# Motor_Connection.net
KiCad netlist of a schematic drawn in Altium Designer
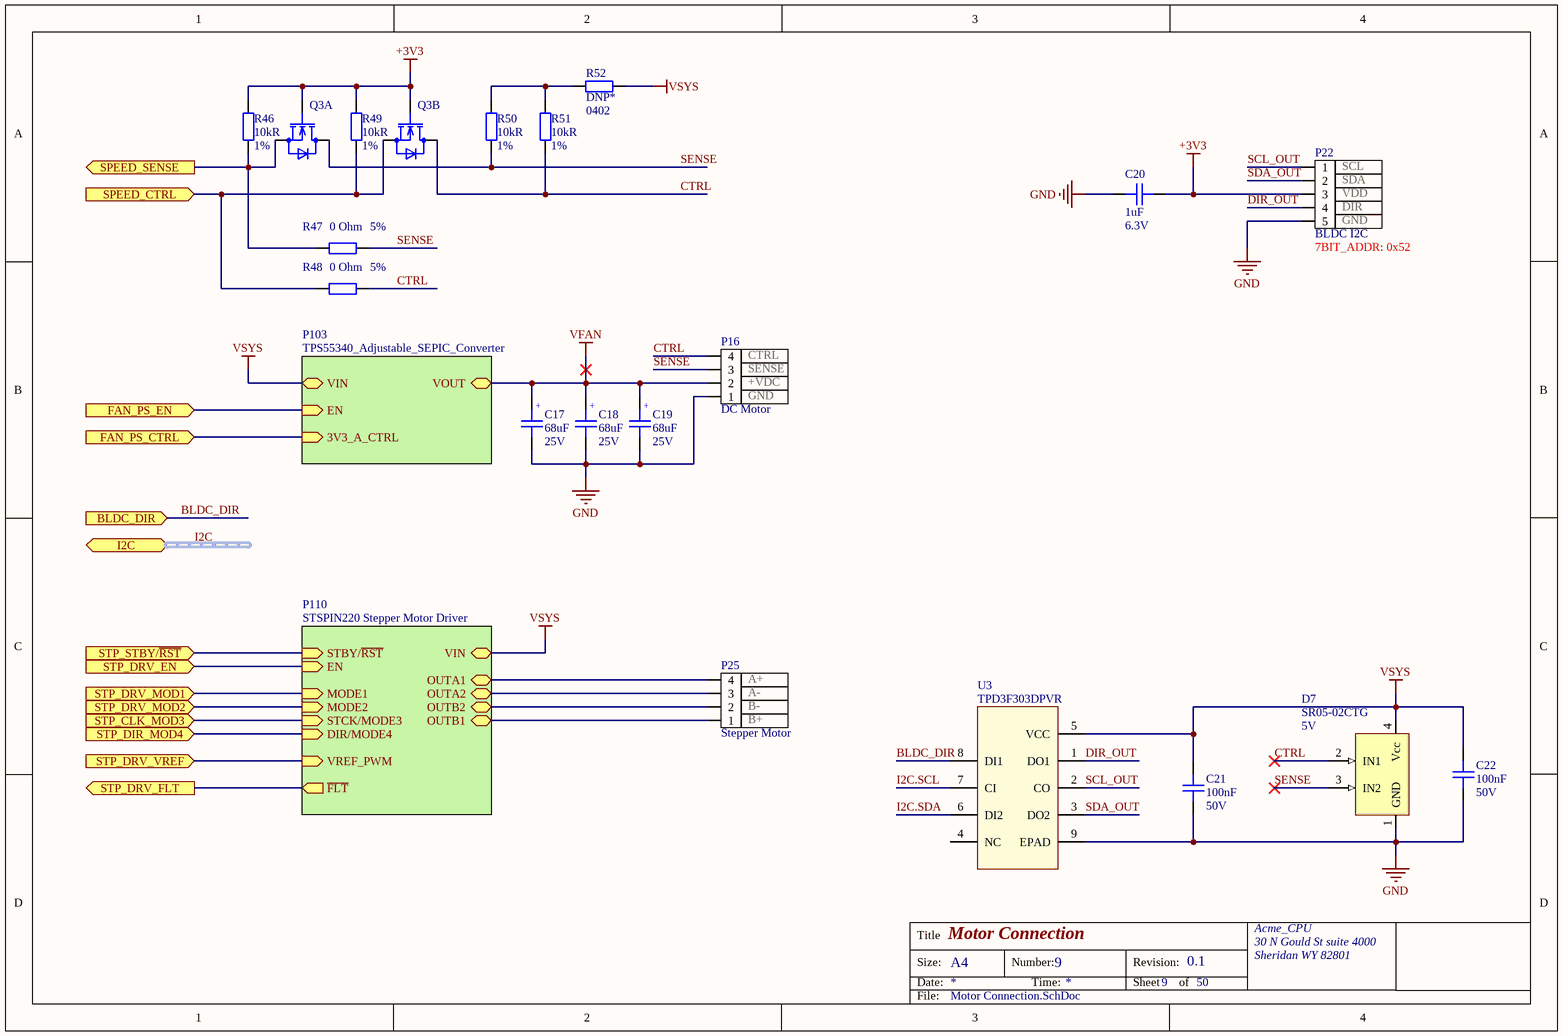
[diagram p0: Motor Connection.SchDoc]

(export (version "E")
  (design (tool "Eeschema 10.0.6"))
  (components
    (comp (ref "C17")
      (value "CAP ALUM 68 UF 20% 25 V SMD")
      (footprint "WCAP-ASLI_6.3x5.5")
      (description "68µF 25V Aluminum Electrolytic Capacitors Radial, Can - SMD  2000 Hrs @ 105°C")
      (fields
        (field (name "MANUFACTURER") "Wurth Elektronik")
        (field (name "MANUFACTURER PART NUMBER") "865080443009")
        (field (name "CAPACITANCE") "68uF")
        (field (name "RATED VOLTAGE") "25V")
      )
      (libsource (lib "capacitors_alum_electr_poly") (part "CAP ALUM 68 UF 20% 25 V SMD"))
    )
    (comp (ref "C18")
      (value "CAP ALUM 68 UF 20% 25 V SMD")
      (footprint "WCAP-ASLI_6.3x5.5")
      (description "68µF 25V Aluminum Electrolytic Capacitors Radial, Can - SMD  2000 Hrs @ 105°C")
      (fields
        (field (name "MANUFACTURER") "Wurth Elektronik")
        (field (name "MANUFACTURER PART NUMBER") "865080443009")
        (field (name "CAPACITANCE") "68uF")
        (field (name "RATED VOLTAGE") "25V")
      )
      (libsource (lib "capacitors_alum_electr_poly") (part "CAP ALUM 68 UF 20% 25 V SMD"))
    )
    (comp (ref "C19")
      (value "CAP ALUM 68 UF 20% 25 V SMD")
      (footprint "WCAP-ASLI_6.3x5.5")
      (description "68µF 25V Aluminum Electrolytic Capacitors Radial, Can - SMD  2000 Hrs @ 105°C")
      (fields
        (field (name "MANUFACTURER") "Wurth Elektronik")
        (field (name "MANUFACTURER PART NUMBER") "865080443009")
        (field (name "CAPACITANCE") "68uF")
        (field (name "RATED VOLTAGE") "25V")
      )
      (libsource (lib "capacitors_alum_electr_poly") (part "CAP ALUM 68 UF 20% 25 V SMD"))
    )
    (comp (ref "C20")
      (value "CAP CER 1UF 6.3V X5R 0402")
      (footprint "C0402")
      (description "1µF ±10% 6.3V Ceramic Capacitor X5R 0402 (1005 Metric)")
      (fields
        (field (name "MANUFACTURER") "Yageo")
        (field (name "MANUFACTURER PART NUMBER") "CC0402KRX5R5BB105")
        (field (name "CAPACITANCE") "1uF")
        (field (name "VOLTAGE RATING") "6.3V")
      )
      (libsource (lib "capacitors_smd") (part "CAP CER 1UF 6.3V X5R 0402"))
    )
    (comp (ref "C21")
      (value "CAP CER 0.1UF 50V X7R 0402")
      (footprint "C0402")
      (description "0.1µF ±10% 50V Ceramic Capacitor X7R 0402 (1005 Metric)")
      (fields
        (field (name "MANUFACTURER") "TDK")
        (field (name "MANUFACTURER PART NUMBER") "CGA2B3X7R1H104K050BB")
        (field (name "CAPACITANCE") "100nF")
        (field (name "VOLTAGE") "50V")
      )
      (libsource (lib "capacitors_smd") (part "CAP CER 0.1UF 50V X7R 0402"))
    )
    (comp (ref "C22")
      (value "CAP CER 0.1UF 50V X7R 0402")
      (footprint "C0402")
      (description "0.1µF ±10% 50V Ceramic Capacitor X7R 0402 (1005 Metric)")
      (fields
        (field (name "MANUFACTURER") "TDK")
        (field (name "MANUFACTURER PART NUMBER") "CGA2B3X7R1H104K050BB")
        (field (name "CAPACITANCE") "100nF")
        (field (name "VOLTAGE") "50V")
      )
      (libsource (lib "capacitors_smd") (part "CAP CER 0.1UF 50V X7R 0402"))
    )
    (comp (ref "D7")
      (value "SR05-02CTG")
      (footprint "SOT-143")
      (description "TVS DIODE 5VWM 18VC SOT143")
      (fields (field (name "MANUFACTURER") "Littelfuse") (field (name "REVERSE STANDOFF VOLTAGE") "5V"))
      (libsource (lib "diodes_tvs") (part "TVS DIODE 5VWM 18VC SOT143"))
    )
    (comp (ref "P16")
      (value "DC Motor")
      (footprint "CONN_S4B-ZR(LF)(SN)")
      (description "Connector Header Through Hole, Right Angle 4 position 0.059\" (1.50mm)")
      (fields
        (field (name "MANUFACTURER") "JST")
        (field (name "MANUFACTURER PART NUMBER") "S4B-ZR(LF)(SN)")
        (field (name "PIN_1") "GND")
        (field (name "PIN_2") "+VDC")
        (field (name "PIN_3") "SENSE")
        (field (name "PIN_4") "CTRL")
      )
      (libsource (lib "connectors_header") (part "CONN HEADER TH R/A 4POS 1.5MM"))
    )
    (comp (ref "P22")
      (value "BLDC I2C")
      (footprint "CONN_S5B-ZR(LF)(SN)")
      (description "Connector Header Through Hole, Right Angle 5 position 0.059\" (1.50mm)")
      (fields
        (field (name "MANUFACTURER") "JST")
        (field (name "MANUFACTURER PART NUMBER") "S5B-ZR(LF)(SN)")
        (field (name "PIN_1") "SCL")
        (field (name "PIN_2") "SDA")
        (field (name "PIN_3") "VDD")
        (field (name "PIN_4") "DIR")
        (field (name "PIN_5") "GND")
        (field (name "7BIT_ADDR") "0x52")
      )
      (libsource (lib "connectors_header") (part "CONN HEADER TH R/A 5POS 1.5MM"))
    )
    (comp (ref "P25")
      (value "Stepper Motor")
      (footprint "CONN_S4B-ZR(LF)(SN)")
      (description "Connector Header Through Hole, Right Angle 4 position 0.059\" (1.50mm)")
      (fields
        (field (name "MANUFACTURER") "JST")
        (field (name "MANUFACTURER PART NUMBER") "S4B-ZR(LF)(SN)")
        (field (name "PIN_1") "B+")
        (field (name "PIN_2") "B-")
        (field (name "PIN_3") "A-")
        (field (name "PIN_4") "A+")
      )
      (libsource (lib "connectors_header") (part "CONN HEADER TH R/A 4POS 1.5MM"))
    )
    (comp (ref "Q3")
      (value "DMN32D2LV-7")
      (footprint "SON_400UV-7_DIO")
      (description "Mosfet Array 2 N-Channel (Dual) 30V 400mA 400mW Surface Mount SOT-563")
      (fields (field (name "MANUFACTURER") "Diodes"))
      (libsource (lib "mosfets") (part "ARRAY MOSFET 2N-CH 30V 0.4A SOT-563"))
    )
    (comp (ref "R46")
      (value "RES SMD 10K OHM 1% 1/16W 0402")
      (footprint "R0402")
      (description "10 kOhms ±1% 0.063W, 1/16W Chip Resistor 0402 (1005 Metric) Moisture Resistant Thick Film")
      (fields
        (field (name "MANUFACTURER PART NUMBER") "RC0402FR-0710KP")
        (field (name "MANUFACTURER") "Yageo")
        (field (name "RESISTANCE") "10kR")
        (field (name "TOLERANCE") "1%")
      )
      (libsource (lib "resistors_smd") (part "RES SMD 10K OHM 1% 1/16W 0402"))
    )
    (comp (ref "R47")
      (value "RES SMD 0 OHM JUMPER 1/16W 0402")
      (footprint "R0402")
      (description "0 Ohms Jumper 0.063W, 1/16W Chip Resistor 0402 (1005 Metric) Moisture Resistant Thick Film")
      (fields
        (field (name "MANUFACTURER") "Yageo")
        (field (name "MANUFACTURER PART NUMBER") "RC0402JR-070RL")
        (field (name "TOLERANCE") "5%")
        (field (name "RESISTANCE") "0 Ohm")
      )
      (libsource (lib "resistors_smd") (part "RES SMD 0 OHM JUMPER 1/16W 0402"))
    )
    (comp (ref "R48")
      (value "RES SMD 0 OHM JUMPER 1/16W 0402")
      (footprint "R0402")
      (description "0 Ohms Jumper 0.063W, 1/16W Chip Resistor 0402 (1005 Metric) Moisture Resistant Thick Film")
      (fields
        (field (name "MANUFACTURER") "Yageo")
        (field (name "MANUFACTURER PART NUMBER") "RC0402JR-070RL")
        (field (name "TOLERANCE") "5%")
        (field (name "RESISTANCE") "0 Ohm")
      )
      (libsource (lib "resistors_smd") (part "RES SMD 0 OHM JUMPER 1/16W 0402"))
    )
    (comp (ref "R49")
      (value "RES SMD 10K OHM 1% 1/16W 0402")
      (footprint "R0402")
      (description "10 kOhms ±1% 0.063W, 1/16W Chip Resistor 0402 (1005 Metric) Moisture Resistant Thick Film")
      (fields
        (field (name "MANUFACTURER PART NUMBER") "RC0402FR-0710KP")
        (field (name "MANUFACTURER") "Yageo")
        (field (name "RESISTANCE") "10kR")
        (field (name "TOLERANCE") "1%")
      )
      (libsource (lib "resistors_smd") (part "RES SMD 10K OHM 1% 1/16W 0402"))
    )
    (comp (ref "R50")
      (value "RES SMD 10K OHM 1% 1/16W 0402")
      (footprint "R0402")
      (description "10 kOhms ±1% 0.063W, 1/16W Chip Resistor 0402 (1005 Metric) Moisture Resistant Thick Film")
      (fields
        (field (name "MANUFACTURER PART NUMBER") "RC0402FR-0710KP")
        (field (name "MANUFACTURER") "Yageo")
        (field (name "RESISTANCE") "10kR")
        (field (name "TOLERANCE") "1%")
      )
      (libsource (lib "resistors_smd") (part "RES SMD 10K OHM 1% 1/16W 0402"))
    )
    (comp (ref "R51")
      (value "RES SMD 10K OHM 1% 1/16W 0402")
      (footprint "R0402")
      (description "10 kOhms ±1% 0.063W, 1/16W Chip Resistor 0402 (1005 Metric) Moisture Resistant Thick Film")
      (fields
        (field (name "MANUFACTURER PART NUMBER") "RC0402FR-0710KP")
        (field (name "MANUFACTURER") "Yageo")
        (field (name "RESISTANCE") "10kR")
        (field (name "TOLERANCE") "1%")
      )
      (libsource (lib "resistors_smd") (part "RES SMD 10K OHM 1% 1/16W 0402"))
    )
    (comp (ref "R52")
      (value "DNP*")
      (footprint "R0402")
      (description "Placeholder for a 0402 resistor")
      (fields (field (name "CASE/PACKAGE") "0402"))
      (libsource (lib "resistors_smd") (part "RES SMD NO BOM 0402"))
    )
    (comp (ref "U3")
      (value "TPD3F303DPVR")
      (footprint "DPV8_1P7X0P4")
      (description "RC (Pi) EMI Filter 2nd Order Low Pass 3 Channel R = 47Ohms, 100Ohms, C = 20pF  8-UFDFN Exposed Pad")
      (fields (field (name "MANUFACTURER") "Texas Instruments"))
      (libsource (lib "diodes_tvs") (part "FILTER RC(PI) ESD SMD  8-UFDFN EP"))
    )
  )
  (nets
    (net (code "2") (name "+3V3") (class "Default")
      (node (ref "C20") (pin "2") (pinfunction "2_2") (pintype "passive"))
      (node (ref "P22") (pin "3") (pinfunction "3_3") (pintype "passive"))
      (node (ref "Q3") (pin "2") (pinfunction "G_2") (pintype "passive"))
      (node (ref "Q3") (pin "5") (pinfunction "G_5") (pintype "passive"))
      (node (ref "R46") (pin "1") (pinfunction "1_1") (pintype "passive"))
      (node (ref "R49") (pin "1") (pinfunction "1_1") (pintype "passive"))
    )
    (net (code "3") (name "/BLDC_DIR") (class "Default")
      (node (ref "U3") (pin "8") (pinfunction "DI1_8") (pintype "passive"))
    )
    (net (code "4") (name "/CTRL") (class "Default")
      (node (ref "D7") (pin "2") (pinfunction "IN1_2") (pintype "input"))
      (node (ref "P16") (pin "4") (pinfunction "4_4") (pintype "passive"))
      (node (ref "Q3") (pin "3") (pinfunction "D_3") (pintype "passive"))
      (node (ref "R48") (pin "2") (pinfunction "2_2") (pintype "passive"))
      (node (ref "R51") (pin "2") (pinfunction "2_2") (pintype "passive"))
    )
    (net (code "5") (name "/DIR_OUT") (class "Default")
      (node (ref "P22") (pin "4") (pinfunction "4_4") (pintype "passive"))
      (node (ref "U3") (pin "1") (pinfunction "DO1_1") (pintype "passive"))
    )
    (net (code "8") (name "/I2C.SCL") (class "Default")
      (node (ref "U3") (pin "7") (pinfunction "CI_7") (pintype "passive"))
    )
    (net (code "9") (name "/I2C.SDA") (class "Default")
      (node (ref "U3") (pin "6") (pinfunction "DI2_6") (pintype "passive"))
    )
    (net (code "10") (name "/OUTA1") (class "Default")
      (node (ref "P25") (pin "4") (pinfunction "4_4") (pintype "passive"))
    )
    (net (code "11") (name "/OUTA2") (class "Default")
      (node (ref "P25") (pin "3") (pinfunction "3_3") (pintype "passive"))
    )
    (net (code "12") (name "/OUTB1") (class "Default")
      (node (ref "P25") (pin "1") (pinfunction "1_1") (pintype "passive"))
    )
    (net (code "13") (name "/OUTB2") (class "Default")
      (node (ref "P25") (pin "2") (pinfunction "2_2") (pintype "passive"))
    )
    (net (code "14") (name "/SCL_OUT") (class "Default")
      (node (ref "P22") (pin "1") (pinfunction "1_1") (pintype "passive"))
      (node (ref "U3") (pin "2") (pinfunction "CO_2") (pintype "passive"))
    )
    (net (code "15") (name "/SDA_OUT") (class "Default")
      (node (ref "P22") (pin "2") (pinfunction "2_2") (pintype "passive"))
      (node (ref "U3") (pin "3") (pinfunction "DO2_3") (pintype "passive"))
    )
    (net (code "16") (name "/SENSE") (class "Default")
      (node (ref "D7") (pin "3") (pinfunction "IN2_3") (pintype "input"))
      (node (ref "P16") (pin "3") (pinfunction "3_3") (pintype "passive"))
      (node (ref "Q3") (pin "6") (pinfunction "D_6") (pintype "passive"))
      (node (ref "R47") (pin "2") (pinfunction "2_2") (pintype "passive"))
      (node (ref "R50") (pin "2") (pinfunction "2_2") (pintype "passive"))
    )
    (net (code "17") (name "/SPEED_CTRL") (class "Default")
      (node (ref "Q3") (pin "4") (pinfunction "S_4") (pintype "passive"))
      (node (ref "R48") (pin "1") (pinfunction "1_1") (pintype "passive"))
      (node (ref "R49") (pin "2") (pinfunction "2_2") (pintype "passive"))
    )
    (net (code "18") (name "/SPEED_SENSE") (class "Default")
      (node (ref "Q3") (pin "1") (pinfunction "S_1") (pintype "passive"))
      (node (ref "R46") (pin "2") (pinfunction "2_2") (pintype "passive"))
      (node (ref "R47") (pin "1") (pinfunction "1_1") (pintype "passive"))
    )
    (net (code "28") (name "GND") (class "Default")
      (node (ref "C17") (pin "2") (pinfunction "2_2") (pintype "passive"))
      (node (ref "C18") (pin "2") (pinfunction "2_2") (pintype "passive"))
      (node (ref "C19") (pin "2") (pinfunction "2_2") (pintype "passive"))
      (node (ref "C20") (pin "1") (pinfunction "1_1") (pintype "passive"))
      (node (ref "C21") (pin "2") (pinfunction "2_2") (pintype "passive"))
      (node (ref "C22") (pin "1") (pinfunction "1_1") (pintype "passive"))
      (node (ref "D7") (pin "1") (pinfunction "GND_1") (pintype "power_in"))
      (node (ref "P16") (pin "1") (pinfunction "1_1") (pintype "passive"))
      (node (ref "P22") (pin "5") (pinfunction "5_5") (pintype "passive"))
      (node (ref "U3") (pin "9") (pinfunction "EPAD_9") (pintype "passive"))
    )
    (net (code "29") (name "Net-(R50-Pad1)") (class "Default")
      (node (ref "R50") (pin "1") (pinfunction "1_1") (pintype "passive"))
      (node (ref "R51") (pin "1") (pinfunction "1_1") (pintype "passive"))
      (node (ref "R52") (pin "2") (pinfunction "2_2") (pintype "passive"))
    )
    (net (code "30") (name "VFAN") (class "Default")
      (node (ref "C17") (pin "1") (pinfunction "1_1") (pintype "passive"))
      (node (ref "C18") (pin "1") (pinfunction "1_1") (pintype "passive"))
      (node (ref "C19") (pin "1") (pinfunction "1_1") (pintype "passive"))
      (node (ref "P16") (pin "2") (pinfunction "2_2") (pintype "passive"))
    )
    (net (code "31") (name "VSYS") (class "Default")
      (node (ref "C21") (pin "1") (pinfunction "1_1") (pintype "passive"))
      (node (ref "C22") (pin "2") (pinfunction "2_2") (pintype "passive"))
      (node (ref "D7") (pin "4") (pinfunction "Vcc_4") (pintype "power_in"))
      (node (ref "R52") (pin "1") (pinfunction "1_1") (pintype "passive"))
      (node (ref "U3") (pin "5") (pinfunction "VCC_5") (pintype "power_in"))
    )
    (net (code "32") (name "unconnected-(U3-NC-Pad4)") (class "Default")
      (node (ref "U3") (pin "4") (pinfunction "NC_4") (pintype "passive"))
    )
  )
)
